# FTDI_1_1.net
KiCad netlist of a schematic drawn in EAGLE
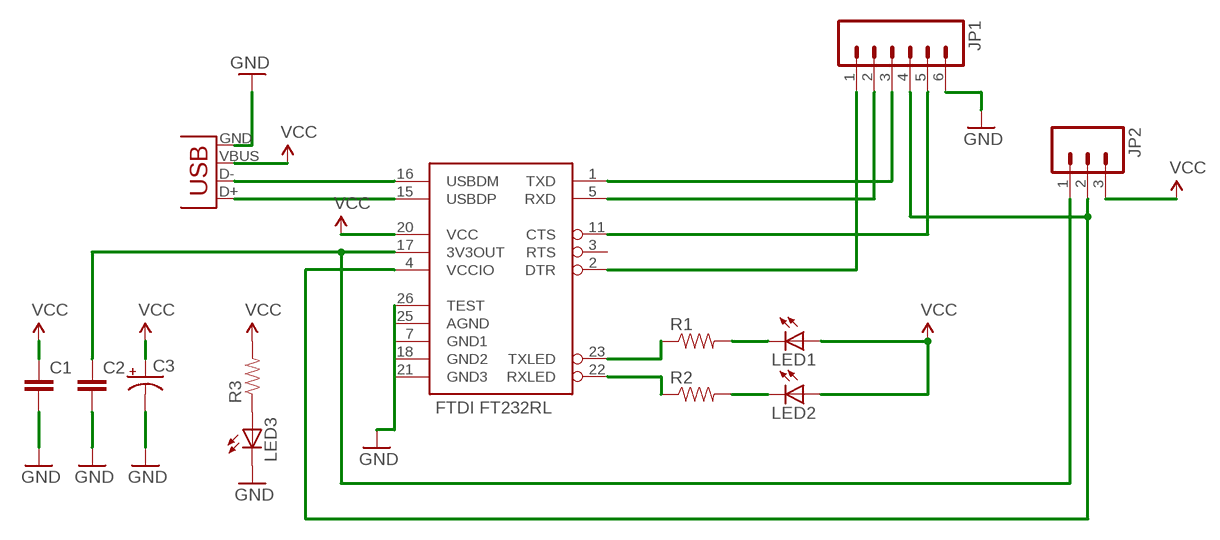
[diagram p0: schematic, sheet 1]

(export (version "E")
  (design (tool "Eeschema 10.0.6"))
  (components
    (comp (ref "C1")
      (value "CAP0603-CAP")
      (footprint "eagle-import:0603-CAP")
      (libsource (lib "eagle-import") (part "CAP0603-CAP"))
    )
    (comp (ref "C2")
      (value "CAP0603-CAP")
      (footprint "eagle-import:0603-CAP")
      (libsource (lib "eagle-import") (part "CAP0603-CAP"))
    )
    (comp (ref "C3")
      (value "CAP_POL1206")
      (footprint "eagle-import:EIA3216")
      (libsource (lib "eagle-import") (part "CAP_POL1206"))
    )
    (comp (ref "JP1")
      (value "M06SIP")
      (footprint "eagle-import:1X06")
      (libsource (lib "eagle-import") (part "M06SIP"))
    )
    (comp (ref "JP2")
      (value "M03PTH")
      (footprint "eagle-import:1X03")
      (libsource (lib "eagle-import") (part "M03PTH"))
    )
    (comp (ref "LED1")
      (value "LED0603")
      (footprint "eagle-import:LED-0603")
      (libsource (lib "eagle-import") (part "LED0603"))
    )
    (comp (ref "LED2")
      (value "LED0603")
      (footprint "eagle-import:LED-0603")
      (libsource (lib "eagle-import") (part "LED0603"))
    )
    (comp (ref "LED3")
      (value "LED0603")
      (footprint "eagle-import:LED-0603")
      (libsource (lib "eagle-import") (part "LED0603"))
    )
    (comp (ref "R1")
      (value "RESISTOR0603-RES")
      (footprint "eagle-import:0603-RES")
      (libsource (lib "eagle-import") (part "RESISTOR0603-RES"))
    )
    (comp (ref "R2")
      (value "RESISTOR0603-RES")
      (footprint "eagle-import:0603-RES")
      (libsource (lib "eagle-import") (part "RESISTOR0603-RES"))
    )
    (comp (ref "R3")
      (value "RESISTOR0603-RES")
      (footprint "eagle-import:0603-RES")
      (libsource (lib "eagle-import") (part "RESISTOR0603-RES"))
    )
    (comp (ref "U1")
      (value "FT232RL-BASICSSOP")
      (footprint "eagle-import:SSOP28DB")
      (libsource (lib "eagle-import") (part "FT232RL-BASICSSOP"))
    )
    (comp (ref "X1")
      (value "USB-SMD-NS")
      (footprint "eagle-import:USB-MINIB-NOSTOP")
      (libsource (lib "eagle-import") (part "USB-SMD-NS"))
    )
  )
  (nets
    (net (code "1") (name "GND") (class "Default")
      (node (ref "C1") (pin "2") (pinfunction "2_2") (pintype "passive"))
      (node (ref "C2") (pin "2") (pinfunction "2_2") (pintype "passive"))
      (node (ref "C3") (pin "C") (pinfunction "-_C") (pintype "passive"))
      (node (ref "JP1") (pin "6") (pinfunction "6_6") (pintype "passive"))
      (node (ref "LED3") (pin "C") (pinfunction "C_C") (pintype "passive"))
      (node (ref "U1") (pin "18") (pinfunction "GND2_18") (pintype "power_in"))
      (node (ref "U1") (pin "21") (pinfunction "GND3_21") (pintype "power_in"))
      (node (ref "U1") (pin "25") (pinfunction "AGND_25") (pintype "power_in"))
      (node (ref "U1") (pin "26") (pinfunction "TEST_26") (pintype "input"))
      (node (ref "U1") (pin "7") (pinfunction "GND1_7") (pintype "power_in"))
      (node (ref "X1") (pin "GND") (pinfunction "GND_GND") (pintype "bidirectional"))
    )
    (net (code "2") (name "Net-(LED1-PadC)") (class "Default")
      (node (ref "LED1") (pin "C") (pinfunction "C_C") (pintype "passive"))
      (node (ref "R1") (pin "2") (pinfunction "2_2") (pintype "passive"))
    )
    (net (code "3") (name "Net-(LED2-PadC)") (class "Default")
      (node (ref "LED2") (pin "C") (pinfunction "C_C") (pintype "passive"))
      (node (ref "R2") (pin "2") (pinfunction "2_2") (pintype "passive"))
    )
    (net (code "4") (name "Net-(LED3-PadA)") (class "Default")
      (node (ref "LED3") (pin "A") (pinfunction "A_A") (pintype "passive"))
      (node (ref "R3") (pin "1") (pinfunction "1_1") (pintype "passive"))
    )
    (net (code "5") (name "Net-(U1-3V3OUT)") (class "Default")
      (node (ref "C2") (pin "1") (pinfunction "1_1") (pintype "passive"))
      (node (ref "JP2") (pin "1") (pinfunction "1_1") (pintype "passive"))
      (node (ref "U1") (pin "17") (pinfunction "3V3OUT_17") (pintype "output"))
    )
    (net (code "6") (name "Net-(U1-CTS)") (class "Default")
      (node (ref "JP1") (pin "5") (pinfunction "5_5") (pintype "passive"))
      (node (ref "U1") (pin "11") (pinfunction "CTS_11") (pintype "bidirectional"))
    )
    (net (code "7") (name "Net-(U1-DTR)") (class "Default")
      (node (ref "JP1") (pin "1") (pinfunction "1_1") (pintype "passive"))
      (node (ref "U1") (pin "2") (pinfunction "DTR_2") (pintype "bidirectional"))
    )
    (net (code "8") (name "Net-(U1-RXD)") (class "Default")
      (node (ref "JP1") (pin "2") (pinfunction "2_2") (pintype "passive"))
      (node (ref "U1") (pin "5") (pinfunction "RXD_5") (pintype "input"))
    )
    (net (code "9") (name "Net-(U1-RXLED)") (class "Default")
      (node (ref "R2") (pin "1") (pinfunction "1_1") (pintype "passive"))
      (node (ref "U1") (pin "22") (pinfunction "RXLED_22") (pintype "bidirectional"))
    )
    (net (code "10") (name "Net-(U1-TXD)") (class "Default")
      (node (ref "JP1") (pin "3") (pinfunction "3_3") (pintype "passive"))
      (node (ref "U1") (pin "1") (pinfunction "TXD_1") (pintype "output"))
    )
    (net (code "11") (name "Net-(U1-TXLED)") (class "Default")
      (node (ref "R1") (pin "1") (pinfunction "1_1") (pintype "passive"))
      (node (ref "U1") (pin "23") (pinfunction "TXLED_23") (pintype "bidirectional"))
    )
    (net (code "12") (name "Net-(U1-USBDM)") (class "Default")
      (node (ref "U1") (pin "16") (pinfunction "USBDM_16") (pintype "bidirectional"))
      (node (ref "X1") (pin "D-") (pinfunction "D-_D-") (pintype "bidirectional"))
    )
    (net (code "13") (name "Net-(U1-USBDP)") (class "Default")
      (node (ref "U1") (pin "15") (pinfunction "USBDP_15") (pintype "bidirectional"))
      (node (ref "X1") (pin "D+") (pinfunction "D+_D+") (pintype "bidirectional"))
    )
    (net (code "14") (name "Net-(U1-VCCIO)") (class "Default")
      (node (ref "JP1") (pin "4") (pinfunction "4_4") (pintype "passive"))
      (node (ref "JP2") (pin "2") (pinfunction "2_2") (pintype "passive"))
      (node (ref "U1") (pin "4") (pinfunction "VCCIO_4") (pintype "power_in"))
    )
    (net (code "15") (name "VCC") (class "Default")
      (node (ref "C1") (pin "1") (pinfunction "1_1") (pintype "passive"))
      (node (ref "C3") (pin "A") (pinfunction "+_A") (pintype "passive"))
      (node (ref "JP2") (pin "3") (pinfunction "3_3") (pintype "passive"))
      (node (ref "LED1") (pin "A") (pinfunction "A_A") (pintype "passive"))
      (node (ref "LED2") (pin "A") (pinfunction "A_A") (pintype "passive"))
      (node (ref "R3") (pin "2") (pinfunction "2_2") (pintype "passive"))
      (node (ref "U1") (pin "20") (pinfunction "VCC_20") (pintype "power_in"))
      (node (ref "X1") (pin "VBUS") (pinfunction "VBUS_VBUS") (pintype "bidirectional"))
    )
    (net (code "16") (name "unconnected-(U1-RTS-Pad3)") (class "Default")
      (node (ref "U1") (pin "3") (pinfunction "RTS_3") (pintype "bidirectional"))
    )
  )
)
